# Sheet1.net
KiCad netlist of a schematic drawn in Altium Designer
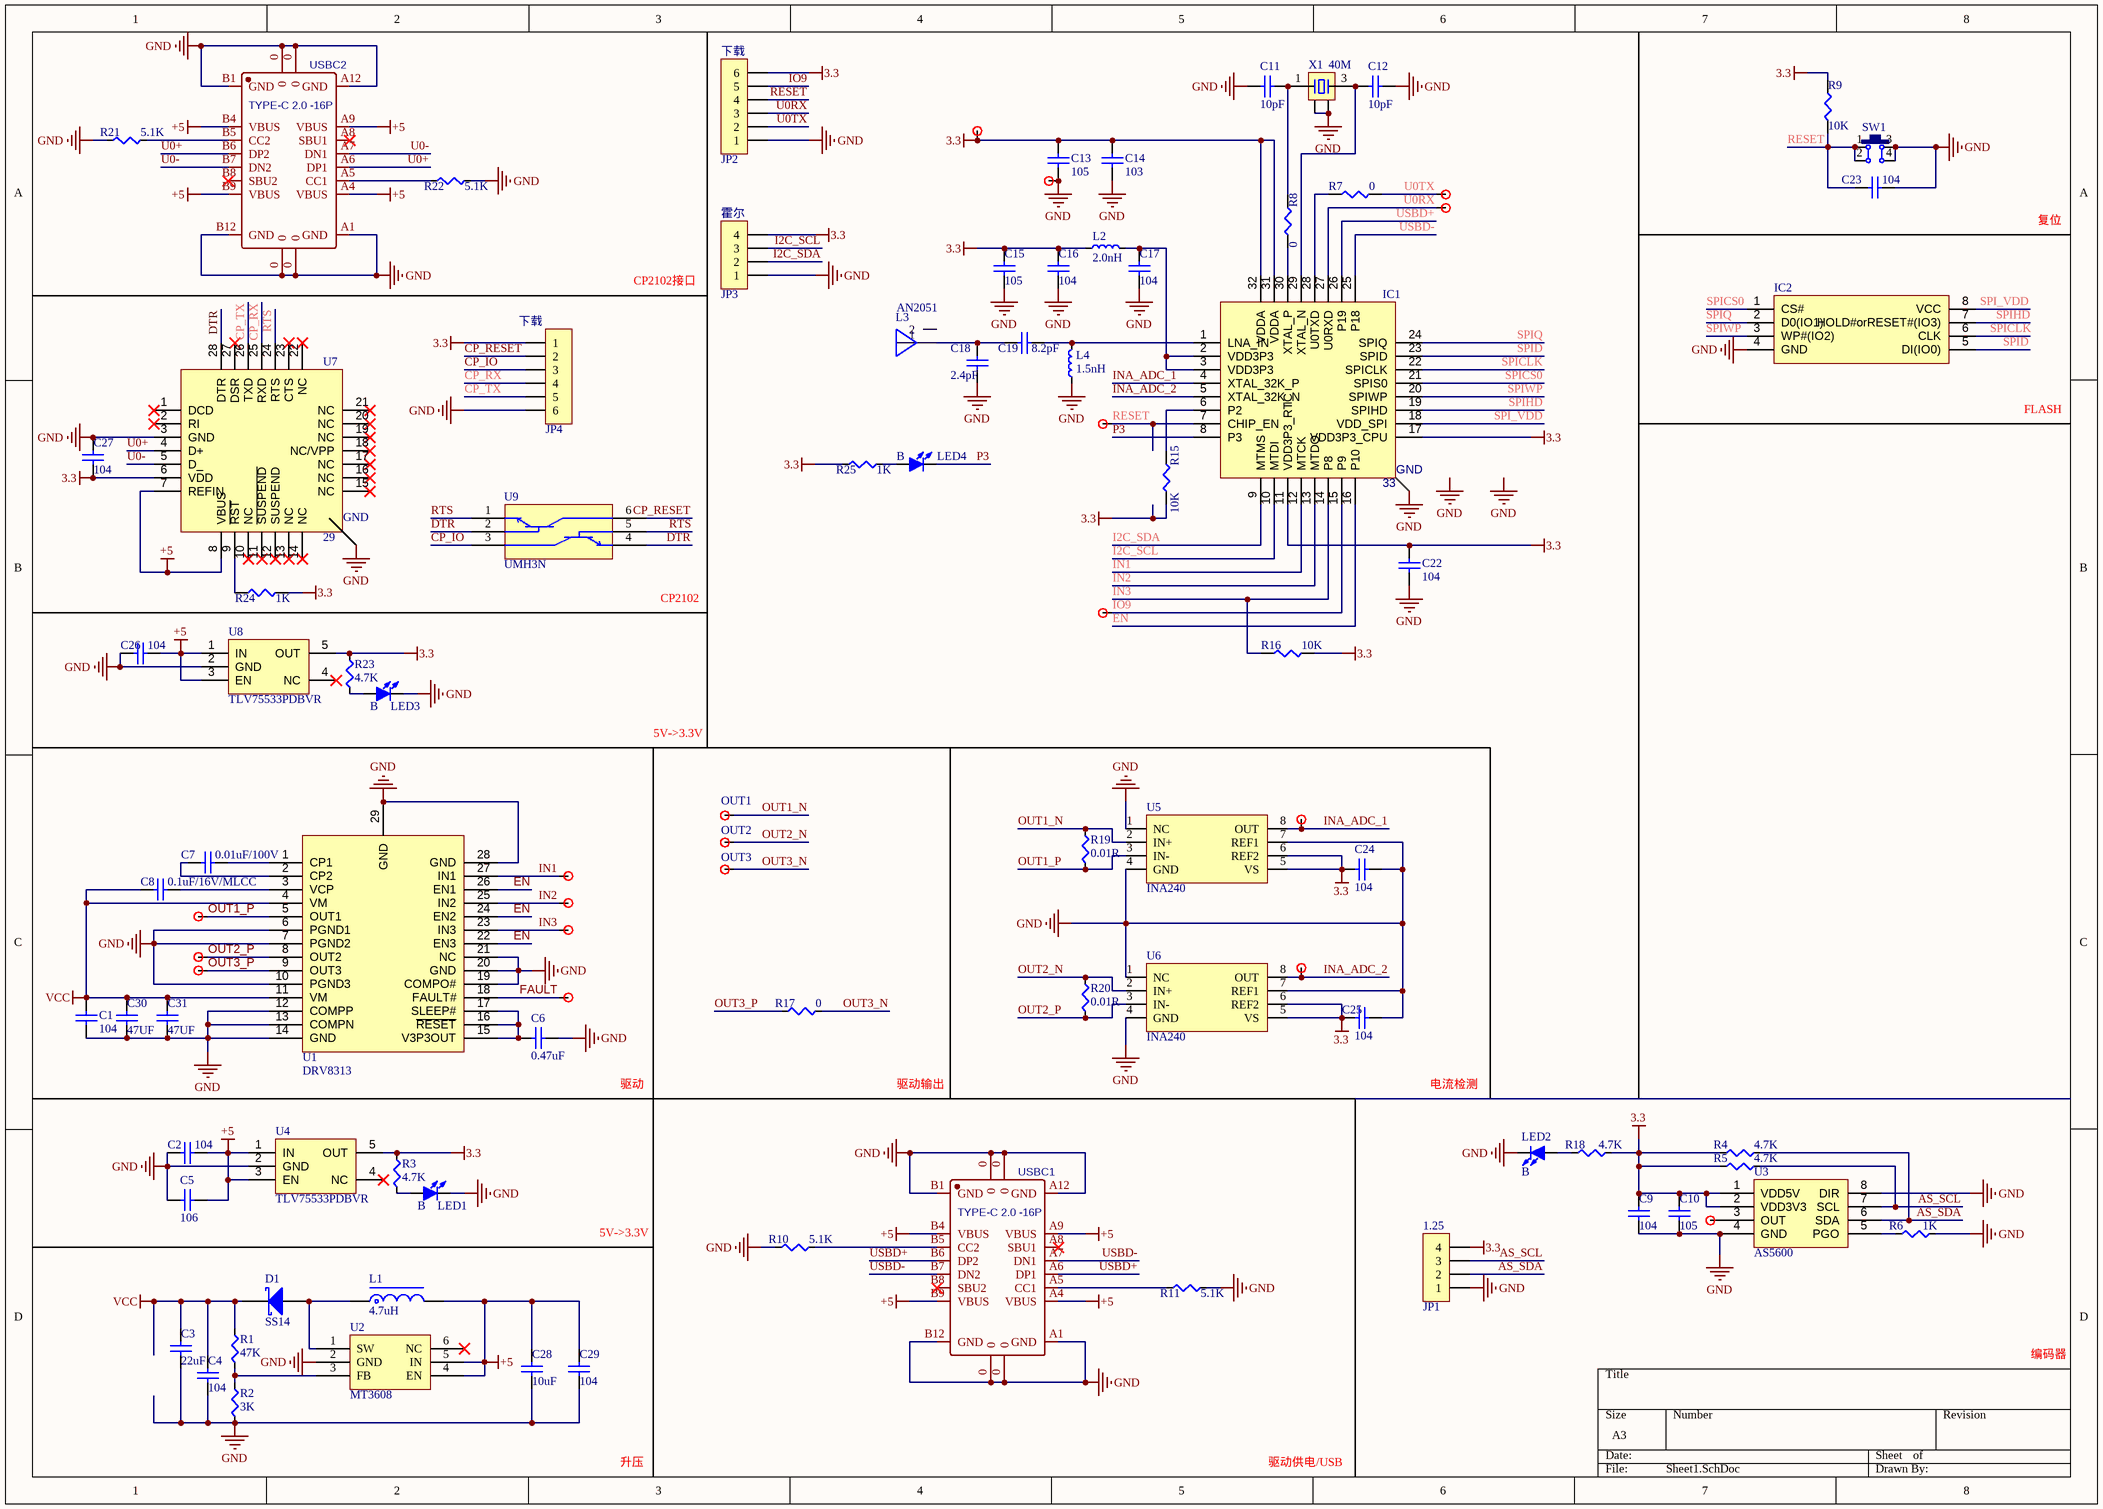
[diagram p0: Sheet1.SchDoc]

(export (version "E")
  (design (tool "Eeschema 10.0.6"))
  (components
    (comp (ref "C1")
      (value "104")
      (footprint "C 0603_L")
      (description "贴片电容")
      (libsource (lib "0.1 - 电阻-电容-电感") (part "C"))
    )
    (comp (ref "C2")
      (value "104")
      (footprint "C 0603_L")
      (description "贴片电容")
      (libsource (lib "0.1 - 电阻-电容-电感") (part "C"))
    )
    (comp (ref "C3")
      (value "22uF")
      (footprint "C 1206_L")
      (description "贴片电容")
      (libsource (lib "0.1 - 电阻-电容-电感") (part "C"))
    )
    (comp (ref "C4")
      (value "104")
      (footprint "C 0603_L")
      (description "贴片电容")
      (libsource (lib "0.1 - 电阻-电容-电感") (part "C"))
    )
    (comp (ref "C5")
      (value "106")
      (footprint "C 1206_L")
      (description "贴片电容")
      (libsource (lib "0.1 - 电阻-电容-电感") (part "C"))
    )
    (comp (ref "C6")
      (value "0.47uF")
      (footprint "C 0603_L")
      (description "贴片电容")
      (libsource (lib "0.1 - 电阻-电容-电感") (part "C"))
    )
    (comp (ref "C7")
      (value "0.01uF/100V")
      (footprint "C 0603_L")
      (description "贴片电容")
      (libsource (lib "0.1 - 电阻-电容-电感") (part "C"))
    )
    (comp (ref "C8")
      (value "0.1uF/16V/MLCC")
      (footprint "C 0603_L")
      (description "贴片电容")
      (libsource (lib "0.1 - 电阻-电容-电感") (part "C"))
    )
    (comp (ref "C9")
      (value "104")
      (footprint "C 0603_L")
      (description "贴片电容")
      (libsource (lib "0.1 - 电阻-电容-电感") (part "C"))
    )
    (comp (ref "C10")
      (value "105")
      (footprint "C 0603_L")
      (description "贴片电容")
      (libsource (lib "0.1 - 电阻-电容-电感") (part "C"))
    )
    (comp (ref "C11")
      (value "10pF")
      (footprint "C 0603_L")
      (description "贴片电容")
      (libsource (lib "0.1 - 电阻-电容-电感") (part "C"))
    )
    (comp (ref "C12")
      (value "10pF")
      (footprint "C 0603_L")
      (description "贴片电容")
      (libsource (lib "0.1 - 电阻-电容-电感") (part "C"))
    )
    (comp (ref "C13")
      (value "105")
      (footprint "C 0603_L")
      (description "贴片电容")
      (libsource (lib "0.1 - 电阻-电容-电感") (part "C"))
    )
    (comp (ref "C14")
      (value "103")
      (footprint "C 0603_L")
      (description "贴片电容")
      (libsource (lib "0.1 - 电阻-电容-电感") (part "C"))
    )
    (comp (ref "C15")
      (value "105")
      (footprint "C 0603_L")
      (description "贴片电容")
      (libsource (lib "0.1 - 电阻-电容-电感") (part "C"))
    )
    (comp (ref "C16")
      (value "104")
      (footprint "C 0603_L")
      (description "贴片电容")
      (libsource (lib "0.1 - 电阻-电容-电感") (part "C"))
    )
    (comp (ref "C17")
      (value "104")
      (footprint "C 0603_L")
      (description "贴片电容")
      (libsource (lib "0.1 - 电阻-电容-电感") (part "C"))
    )
    (comp (ref "C18")
      (value "2.4pF")
      (footprint "C 0603_L")
      (description "贴片电容")
      (libsource (lib "0.1 - 电阻-电容-电感") (part "C"))
    )
    (comp (ref "C19")
      (value "8.2pF")
      (footprint "C 0603_L")
      (description "贴片电容")
      (libsource (lib "0.1 - 电阻-电容-电感") (part "C"))
    )
    (comp (ref "C22")
      (value "104")
      (footprint "C 0603_L")
      (description "贴片电容")
      (libsource (lib "0.1 - 电阻-电容-电感") (part "C"))
    )
    (comp (ref "C23")
      (value "104")
      (footprint "C 0603_L")
      (description "贴片电容")
      (libsource (lib "0.1 - 电阻-电容-电感") (part "C"))
    )
    (comp (ref "C24")
      (value "104")
      (footprint "C 0603_L")
      (description "贴片电容")
      (libsource (lib "0.1 - 电阻-电容-电感") (part "C"))
    )
    (comp (ref "C25")
      (value "104")
      (footprint "C 0603_L")
      (description "贴片电容")
      (libsource (lib "0.1 - 电阻-电容-电感") (part "C"))
    )
    (comp (ref "C26")
      (value "104")
      (footprint "C 0603_L")
      (description "贴片电容")
      (libsource (lib "0.1 - 电阻-电容-电感") (part "C"))
    )
    (comp (ref "C27")
      (value "104")
      (footprint "C 0603_L")
      (description "贴片电容")
      (libsource (lib "0.1 - 电阻-电容-电感") (part "C"))
    )
    (comp (ref "C28")
      (value "10uF")
      (footprint "C 1206_L")
      (description "贴片电容")
      (libsource (lib "0.1 - 电阻-电容-电感") (part "C"))
    )
    (comp (ref "C29")
      (value "104")
      (footprint "C 0603_L")
      (description "贴片电容")
      (libsource (lib "0.1 - 电阻-电容-电感") (part "C"))
    )
    (comp (ref "C30")
      (value "47UF")
      (footprint "C 1206_L")
      (description "贴片电容")
      (libsource (lib "0.1 - 电阻-电容-电感") (part "C"))
    )
    (comp (ref "C31")
      (value "47UF")
      (footprint "C 1206_L")
      (description "贴片电容")
      (libsource (lib "0.1 - 电阻-电容-电感") (part "C"))
    )
    (comp (ref "D1")
      (value "SS14")
      (footprint "SMA")
      (description "肖特基二极管")
      (libsource (lib "0.2 - 二极管-整流桥") (part "SS14"))
    )
    (comp (ref "HP1")
      (value "HP")
      (footprint "HP1x0.5")
      (description "引脚测试点")
      (libsource (lib "6.6 - 焊盘") (part "HP"))
    )
    (comp (ref "HP2")
      (value "HP")
      (footprint "HP1x0.5")
      (description "引脚测试点")
      (libsource (lib "6.6 - 焊盘") (part "HP"))
    )
    (comp (ref "HP3")
      (value "HP")
      (footprint "HP1x0.5")
      (description "引脚测试点")
      (libsource (lib "6.6 - 焊盘") (part "HP"))
    )
    (comp (ref "HP4")
      (value "HP")
      (footprint "HP1x0.5")
      (description "引脚测试点")
      (libsource (lib "6.6 - 焊盘") (part "HP"))
    )
    (comp (ref "HP5")
      (value "HP")
      (footprint "HP1x0.5")
      (description "引脚测试点")
      (libsource (lib "6.6 - 焊盘") (part "HP"))
    )
    (comp (ref "HP6")
      (value "HP")
      (footprint "HP1x0.5")
      (description "引脚测试点")
      (libsource (lib "6.6 - 焊盘") (part "HP"))
    )
    (comp (ref "HP7")
      (value "HP")
      (footprint "HP1x0.5")
      (description "引脚测试点")
      (libsource (lib "6.6 - 焊盘") (part "HP"))
    )
    (comp (ref "HP8")
      (value "HP")
      (footprint "HP1x0.5")
      (description "引脚测试点")
      (libsource (lib "6.6 - 焊盘") (part "HP"))
    )
    (comp (ref "HP9")
      (value "OUT1")
      (footprint "HP1x0.5")
      (description "引脚测试点")
      (libsource (lib "6.6 - 焊盘") (part "HP"))
    )
    (comp (ref "HP10")
      (value "OUT2")
      (footprint "HP1x0.5")
      (description "引脚测试点")
      (libsource (lib "6.6 - 焊盘") (part "HP"))
    )
    (comp (ref "HP11")
      (value "OUT3")
      (footprint "HP1x0.5")
      (description "引脚测试点")
      (libsource (lib "6.6 - 焊盘") (part "HP"))
    )
    (comp (ref "HP12")
      (value "HP")
      (footprint "HP1x0.5")
      (description "引脚测试点")
      (libsource (lib "6.6 - 焊盘") (part "HP"))
    )
    (comp (ref "HP13")
      (value "HP")
      (footprint "HP1x0.5")
      (description "引脚测试点")
      (libsource (lib "6.6 - 焊盘") (part "HP"))
    )
    (comp (ref "HP14")
      (value "HP")
      (footprint "HP1x0.5")
      (description "引脚测试点")
      (libsource (lib "6.6 - 焊盘") (part "HP"))
    )
    (comp (ref "HP15")
      (value "HP")
      (footprint "HP1x0.5")
      (description "引脚测试点")
      (libsource (lib "6.6 - 焊盘") (part "HP"))
    )
    (comp (ref "HP16")
      (value "HP")
      (footprint "HP1x0.5")
      (description "引脚测试点")
      (libsource (lib "6.6 - 焊盘") (part "HP"))
    )
    (comp (ref "HP17")
      (value "HP")
      (footprint "HP1x0.5")
      (description "引脚测试点")
      (libsource (lib "6.6 - 焊盘") (part "HP"))
    )
    (comp (ref "HP18")
      (value "HP")
      (footprint "HP1x0.5")
      (description "引脚测试点")
      (libsource (lib "6.6 - 焊盘") (part "HP"))
    )
    (comp (ref "HP19")
      (value "HP")
      (footprint "HP1x0.5")
      (description "引脚测试点")
      (libsource (lib "6.6 - 焊盘") (part "HP"))
    )
    (comp (ref "IC1")
      (value "ESP32-C3")
      (footprint "ESP32-C3")
      (description "ESP32-C3 QFN-32(5x5)")
      (libsource (lib "ESP32") (part "ESP32-C3"))
    )
    (comp (ref "IC2")
      (value "W25Q64")
      (footprint "SOIC-8W")
      (libsource (lib "1.2 - 存储器-传感元件") (part "W25Q64"))
    )
    (comp (ref "JP1")
      (value "HDR-1X4")
      (footprint "MX 1.25-WI-4P")
      (description "4P接插件")
      (libsource (lib "5.0 - 接插件-脚距1.25") (part "Header 4"))
    )
    (comp (ref "JP2")
      (value "HDR-1X6")
      (footprint "MX 1.25-WI-6P")
      (description "6P接插件")
      (libsource (lib "5.0 - 接插件-脚距1.25") (part "Header 6"))
    )
    (comp (ref "JP3")
      (value "HDR-1X4")
      (footprint "MX 1.25-WI-4P")
      (description "4P接插件")
      (libsource (lib "5.0 - 接插件-脚距1.25") (part "Header 4"))
    )
    (comp (ref "JP4")
      (value "HDR-1X6")
      (footprint "MX 1.25-WI-6P")
      (description "6P接插件")
      (libsource (lib "") (part "Header 6_1"))
    )
    (comp (ref "L1")
      (value "4.7uH")
      (footprint "NR4020")
      (description "NR磁胶电感")
      (libsource (lib "0.1 - 电阻-电容-电感") (part "L-NR"))
    )
    (comp (ref "L2")
      (value "2.0nH")
      (footprint "L 0603")
      (description "小功率贴片电感")
      (libsource (lib "0.1 - 电阻-电容-电感") (part "L"))
    )
    (comp (ref "L3")
      (value "AN2051")
      (footprint "AN2051-245 2.4G")
      (description "AN2051-245 2.4G蓝牙wifi 贴片 2051")
      (libsource (lib "1.8 - WiFi天线-SMA射频座") (part "AN2051"))
    )
    (comp (ref "L4")
      (value "1.5nH")
      (footprint "L 0603")
      (description "小功率贴片电感")
      (libsource (lib "0.1 - 电阻-电容-电感") (part "L"))
    )
    (comp (ref "LED1")
      (value "B")
      (footprint "LED 0603B")
      (description "贴片LED")
      (libsource (lib "0.3 - LED发光二极管") (part "B"))
    )
    (comp (ref "LED2")
      (value "B")
      (footprint "LED 0603B")
      (description "贴片LED")
      (libsource (lib "0.3 - LED发光二极管") (part "B"))
    )
    (comp (ref "LED3")
      (value "B")
      (footprint "LED 0603B")
      (description "贴片LED")
      (libsource (lib "0.3 - LED发光二极管") (part "B"))
    )
    (comp (ref "LED4")
      (value "B")
      (footprint "LED 0603B")
      (description "贴片LED")
      (libsource (lib "0.3 - LED发光二极管") (part "B"))
    )
    (comp (ref "R1")
      (value "47K")
      (footprint "R 0603_L")
      (description "贴片电阻")
      (libsource (lib "") (part "R_1"))
    )
    (comp (ref "R2")
      (value "3K")
      (footprint "R 0603_L")
      (description "贴片电阻")
      (libsource (lib "") (part "R_1"))
    )
    (comp (ref "R3")
      (value "4.7K")
      (footprint "R 0603_L")
      (description "贴片电阻")
      (libsource (lib "") (part "R_1"))
    )
    (comp (ref "R4")
      (value "4.7K")
      (footprint "R 0603_L")
      (description "贴片电阻")
      (libsource (lib "") (part "R_1"))
    )
    (comp (ref "R5")
      (value "4.7K")
      (footprint "R 0603_L")
      (description "贴片电阻")
      (libsource (lib "") (part "R_1"))
    )
    (comp (ref "R6")
      (value "1K")
      (footprint "R 0603_L")
      (description "贴片电阻")
      (libsource (lib "") (part "R_1"))
    )
    (comp (ref "R7")
      (value "0")
      (footprint "R 0603_L")
      (description "贴片电阻")
      (libsource (lib "0.1 - 电阻-电容-电感") (part "R"))
    )
    (comp (ref "R8")
      (value "0")
      (footprint "R 0603_L")
      (description "贴片电阻")
      (libsource (lib "0.1 - 电阻-电容-电感") (part "R"))
    )
    (comp (ref "R9")
      (value "10K")
      (footprint "R 0603_L")
      (description "贴片电阻")
      (libsource (lib "0.1 - 电阻-电容-电感") (part "R"))
    )
    (comp (ref "R10")
      (value "5.1K")
      (footprint "R 0603_L")
      (description "贴片电阻")
      (libsource (lib "") (part "R_1"))
    )
    (comp (ref "R11")
      (value "5.1K")
      (footprint "R 0603_L")
      (description "贴片电阻")
      (libsource (lib "") (part "R_1"))
    )
    (comp (ref "R15")
      (value "10K")
      (footprint "R 0603_L")
      (description "贴片电阻")
      (libsource (lib "0.1 - 电阻-电容-电感") (part "R"))
    )
    (comp (ref "R16")
      (value "10K")
      (footprint "R 0603_L")
      (description "贴片电阻")
      (libsource (lib "0.1 - 电阻-电容-电感") (part "R"))
    )
    (comp (ref "R17")
      (value "0")
      (footprint "R 0603_L")
      (description "贴片电阻")
      (libsource (lib "") (part "R_1"))
    )
    (comp (ref "R18")
      (value "4.7K")
      (footprint "R 0603_L")
      (description "贴片电阻")
      (libsource (lib "") (part "R_1"))
    )
    (comp (ref "R19")
      (value "0.01R")
      (footprint "R 1206_L")
      (description "贴片电阻")
      (libsource (lib "") (part "R_1"))
    )
    (comp (ref "R20")
      (value "0.01R")
      (footprint "R 1206_L")
      (description "贴片电阻")
      (libsource (lib "") (part "R_1"))
    )
    (comp (ref "R21")
      (value "5.1K")
      (footprint "R 0603_L")
      (description "贴片电阻")
      (libsource (lib "") (part "R_1"))
    )
    (comp (ref "R22")
      (value "5.1K")
      (footprint "R 0603_L")
      (description "贴片电阻")
      (libsource (lib "") (part "R_1"))
    )
    (comp (ref "R23")
      (value "4.7K")
      (footprint "R 0603_L")
      (description "贴片电阻")
      (libsource (lib "") (part "R_1"))
    )
    (comp (ref "R24")
      (value "1K")
      (footprint "R 0603_L")
      (description "贴片电阻")
      (libsource (lib "0.1 - 电阻-电容-电感") (part "R"))
    )
    (comp (ref "R25")
      (value "1K")
      (footprint "R 0603_L")
      (description "贴片电阻")
      (libsource (lib "") (part "R_1"))
    )
    (comp (ref "SW1")
      (value "3.2x4.2x5")
      (footprint "TSW SMD 3.2*4.2*2.5")
      (description "贴片4.2*3.2轻触开关")
      (libsource (lib "0.7 - 常用按键-开关-蜂鸣器-电池") (part "TSW SMD-3.2x4.2"))
    )
    (comp (ref "U1")
      (value "DRV8313")
      (footprint "HTSSOP-28-EP-4.5mm")
      (description "DRV8313 无刷直流BLDC 8V~60V三路半H桥驱动器IC")
      (libsource (lib "1.0 - 常见芯片") (part "DRV8313"))
    )
    (comp (ref "U2")
      (value "MT3608")
      (footprint "SOT23-6L")
      (description "DCDC 升压1.2MHZ 2A\r\n97%")
      (libsource (lib "1.1 - 电源类芯片") (part "MT3608"))
    )
    (comp (ref "U3")
      (value "AS5600")
      (footprint "SOIC-8")
      (description "AS5600 12bit磁角度位置传感器")
      (libsource (lib "1.0 - 常见芯片") (part "AS5600"))
    )
    (comp (ref "U4")
      (value "TLV75533PDBVR")
      (footprint "SOT23-5L")
      (description "Vout:3.3V;Vin:1.45~5.5V,500ma;低压降")
      (libsource (lib "1.1 - 电源类芯片") (part "TLV75533PDBVR"))
    )
    (comp (ref "U5")
      (value "INA240")
      (footprint "TSSOP8_N")
      (description "具有增强的 PWM 抑制能力的 -4V 至 80V、双向、超精密电流感应放大器")
      (libsource (lib "1.1 - 电源类芯片") (part "INA240"))
    )
    (comp (ref "U6")
      (value "INA240")
      (footprint "TSSOP8_N")
      (description "具有增强的 PWM 抑制能力的 -4V 至 80V、双向、超精密电流感应放大器")
      (libsource (lib "1.1 - 电源类芯片") (part "INA240"))
    )
    (comp (ref "U7")
      (value "CP2102")
      (footprint "QFN28 5x5_M")
      (description "USB转TTL")
      (libsource (lib "1.0 - 常见芯片") (part "CP2102"))
    )
    (comp (ref "U8")
      (value "TLV75533PDBVR")
      (footprint "SOT23-5L")
      (description "Vout:3.3V;Vin:1.45~5.5V,500ma;低压降")
      (libsource (lib "1.1 - 电源类芯片") (part "TLV75533PDBVR"))
    )
    (comp (ref "U9")
      (value "UMH3N")
      (footprint "SOT-363")
      (description "2NPN预偏式(双)")
      (libsource (lib "0.4 - 三极管-场效应管-可控硅") (part "UMH3N"))
    )
    (comp (ref "USBC1")
      (value "TYPE-C 2.0 -16P")
      (footprint "USB-C-SMD_TYPE-C-USB-5")
      (description "USB2.0 Type-C 母座 16Pin")
      (libsource (lib "0.8 - 以太网-音频-USB插座") (part "USB2.0 Type-C 16Pin母座"))
    )
    (comp (ref "USBC2")
      (value "TYPE-C 2.0 -16P")
      (footprint "USB-C-SMD_TYPE-C-USB-5")
      (description "USB2.0 Type-C 母座 16Pin")
      (libsource (lib "0.8 - 以太网-音频-USB插座") (part "USB2.0 Type-C 16Pin母座"))
    )
    (comp (ref "X1")
      (value "40M")
      (footprint "OSC 3225-4P")
      (description "4脚无源晶振")
      (libsource (lib "0.5 - 保险丝-晶振-光耦") (part "XTAL-4P"))
    )
  )
  (nets
    (net (code "1") (name "+5") (class "Default")
      (node (ref "C2") (pin "2") (pinfunction "2_2") (pintype "passive"))
      (node (ref "C26") (pin "2") (pinfunction "2_2") (pintype "passive"))
      (node (ref "C28") (pin "2") (pinfunction "2_2") (pintype "passive"))
      (node (ref "C29") (pin "2") (pinfunction "2_2") (pintype "passive"))
      (node (ref "C5") (pin "1") (pinfunction "1_1") (pintype "passive"))
      (node (ref "L1") (pin "2") (pinfunction "2_2") (pintype "passive"))
      (node (ref "U2") (pin "4") (pinfunction "EN_4") (pintype "passive"))
      (node (ref "U2") (pin "5") (pinfunction "IN_5") (pintype "passive"))
      (node (ref "U4") (pin "1") (pinfunction "IN_1") (pintype "passive"))
      (node (ref "U4") (pin "3") (pinfunction "EN_3") (pintype "passive"))
      (node (ref "U7") (pin "7") (pinfunction "REFIN_7") (pintype "passive"))
      (node (ref "U7") (pin "8") (pinfunction "VBUS_8") (pintype "passive"))
      (node (ref "U8") (pin "1") (pinfunction "IN_1") (pintype "passive"))
      (node (ref "U8") (pin "3") (pinfunction "EN_3") (pintype "passive"))
      (node (ref "USBC1") (pin "A4") (pinfunction "VBUS_A4") (pintype "passive"))
      (node (ref "USBC1") (pin "A9") (pinfunction "VBUS_A9") (pintype "passive"))
      (node (ref "USBC1") (pin "B4") (pinfunction "VBUS_B4") (pintype "passive"))
      (node (ref "USBC1") (pin "B9") (pinfunction "VBUS_B9") (pintype "passive"))
      (node (ref "USBC2") (pin "A4") (pinfunction "VBUS_A4") (pintype "passive"))
      (node (ref "USBC2") (pin "A9") (pinfunction "VBUS_A9") (pintype "passive"))
      (node (ref "USBC2") (pin "B4") (pinfunction "VBUS_B4") (pintype "passive"))
      (node (ref "USBC2") (pin "B9") (pinfunction "VBUS_B9") (pintype "passive"))
    )
    (net (code "2") (name "/AS_SCL") (class "Default")
      (node (ref "JP1") (pin "3") (pinfunction "3_3") (pintype "passive"))
      (node (ref "R5") (pin "2") (pinfunction "2_2") (pintype "passive"))
      (node (ref "U3") (pin "7") (pinfunction "SCL_7") (pintype "passive"))
    )
    (net (code "3") (name "/AS_SDA") (class "Default")
      (node (ref "JP1") (pin "2") (pinfunction "2_2") (pintype "passive"))
      (node (ref "R4") (pin "2") (pinfunction "2_2") (pintype "passive"))
      (node (ref "U3") (pin "6") (pinfunction "SDA_6") (pintype "passive"))
    )
    (net (code "4") (name "/CP_IO") (class "Default")
      (node (ref "JP4") (pin "3") (pinfunction "3_3") (pintype "passive"))
      (node (ref "U9") (pin "3") (pinfunction "C2_3") (pintype "passive"))
    )
    (net (code "5") (name "/CP_RESET") (class "Default")
      (node (ref "JP4") (pin "2") (pinfunction "2_2") (pintype "passive"))
      (node (ref "U9") (pin "6") (pinfunction "C1_6") (pintype "passive"))
    )
    (net (code "6") (name "/CP_RX") (class "Default")
      (node (ref "JP4") (pin "4") (pinfunction "4_4") (pintype "passive"))
      (node (ref "U7") (pin "25") (pinfunction "RXD_25") (pintype "passive"))
    )
    (net (code "7") (name "/CP_TX") (class "Default")
      (node (ref "JP4") (pin "5") (pinfunction "5_5") (pintype "passive"))
      (node (ref "U7") (pin "26") (pinfunction "TXD_26") (pintype "passive"))
    )
    (net (code "8") (name "/DTR") (class "Default")
      (node (ref "U7") (pin "28") (pinfunction "DTR_28") (pintype "passive"))
      (node (ref "U9") (pin "2") (pinfunction "B2_2") (pintype "passive"))
      (node (ref "U9") (pin "4") (pinfunction "E2_4") (pintype "passive"))
    )
    (net (code "9") (name "/EN") (class "Default")
      (node (ref "IC1") (pin "16") (pinfunction "P10_16") (pintype "power_in"))
      (node (ref "U1") (pin "22") (pinfunction "EN3_22") (pintype "passive"))
      (node (ref "U1") (pin "24") (pinfunction "EN2_24") (pintype "passive"))
      (node (ref "U1") (pin "26") (pinfunction "EN1_26") (pintype "passive"))
    )
    (net (code "10") (name "/FAULT") (class "Default")
      (node (ref "HP7") (pin "1") (pinfunction "1_1") (pintype "passive"))
      (node (ref "U1") (pin "18") (pinfunction "FAULT#_18") (pintype "passive"))
    )
    (net (code "11") (name "/I2C_SCL") (class "Default")
      (node (ref "IC1") (pin "10") (pinfunction "MTDI_10") (pintype "power_in"))
      (node (ref "JP3") (pin "3") (pinfunction "3_3") (pintype "passive"))
    )
    (net (code "12") (name "/I2C_SDA") (class "Default")
      (node (ref "IC1") (pin "9") (pinfunction "MTMS_9") (pintype "power_in"))
      (node (ref "JP3") (pin "2") (pinfunction "2_2") (pintype "passive"))
    )
    (net (code "13") (name "/IN1") (class "Default")
      (node (ref "HP1") (pin "1") (pinfunction "1_1") (pintype "passive"))
      (node (ref "IC1") (pin "12") (pinfunction "MTCK_12") (pintype "power_in"))
      (node (ref "U1") (pin "27") (pinfunction "IN1_27") (pintype "passive"))
    )
    (net (code "14") (name "/IN2") (class "Default")
      (node (ref "HP2") (pin "1") (pinfunction "1_1") (pintype "passive"))
      (node (ref "IC1") (pin "13") (pinfunction "MTDO_13") (pintype "power_in"))
      (node (ref "U1") (pin "25") (pinfunction "IN2_25") (pintype "passive"))
    )
    (net (code "15") (name "/IN3") (class "Default")
      (node (ref "HP4") (pin "1") (pinfunction "1_1") (pintype "passive"))
      (node (ref "IC1") (pin "14") (pinfunction "P8_14") (pintype "power_in"))
      (node (ref "R16") (pin "1") (pinfunction "1_1") (pintype "passive"))
      (node (ref "U1") (pin "23") (pinfunction "IN3_23") (pintype "passive"))
    )
    (net (code "16") (name "/INA_ADC_1") (class "Default")
      (node (ref "HP12") (pin "1") (pinfunction "1_1") (pintype "passive"))
      (node (ref "IC1") (pin "4") (pinfunction "XTAL_32K_P_4") (pintype "power_in"))
      (node (ref "U5") (pin "8") (pinfunction "OUT_8") (pintype "passive"))
    )
    (net (code "17") (name "/INA_ADC_2") (class "Default")
      (node (ref "HP14") (pin "1") (pinfunction "1_1") (pintype "passive"))
      (node (ref "IC1") (pin "5") (pinfunction "XTAL_32K_N_5") (pintype "power_in"))
      (node (ref "U6") (pin "8") (pinfunction "OUT_8") (pintype "passive"))
    )
    (net (code "18") (name "/IO9") (class "Default")
      (node (ref "HP17") (pin "1") (pinfunction "1_1") (pintype "passive"))
      (node (ref "IC1") (pin "15") (pinfunction "P9_15") (pintype "power_in"))
      (node (ref "JP2") (pin "5") (pinfunction "5_5") (pintype "passive"))
    )
    (net (code "19") (name "/OUT1_N") (class "Default")
      (node (ref "HP9") (pin "1") (pinfunction "1_1") (pintype "passive"))
      (node (ref "R19") (pin "2") (pinfunction "2_2") (pintype "passive"))
      (node (ref "U5") (pin "2") (pinfunction "IN+_2") (pintype "passive"))
    )
    (net (code "20") (name "/OUT1_P") (class "Default")
      (node (ref "HP3") (pin "1") (pinfunction "1_1") (pintype "passive"))
      (node (ref "R19") (pin "1") (pinfunction "1_1") (pintype "passive"))
      (node (ref "U1") (pin "5") (pinfunction "OUT1_5") (pintype "passive"))
      (node (ref "U5") (pin "3") (pinfunction "IN-_3") (pintype "passive"))
    )
    (net (code "21") (name "/OUT2_N") (class "Default")
      (node (ref "HP10") (pin "1") (pinfunction "1_1") (pintype "passive"))
      (node (ref "R20") (pin "2") (pinfunction "2_2") (pintype "passive"))
      (node (ref "U6") (pin "2") (pinfunction "IN+_2") (pintype "passive"))
    )
    (net (code "22") (name "/OUT2_P") (class "Default")
      (node (ref "HP5") (pin "1") (pinfunction "1_1") (pintype "passive"))
      (node (ref "R20") (pin "1") (pinfunction "1_1") (pintype "passive"))
      (node (ref "U1") (pin "8") (pinfunction "OUT2_8") (pintype "passive"))
      (node (ref "U6") (pin "3") (pinfunction "IN-_3") (pintype "passive"))
    )
    (net (code "23") (name "/OUT3_N") (class "Default")
      (node (ref "HP11") (pin "1") (pinfunction "1_1") (pintype "passive"))
      (node (ref "R17") (pin "2") (pinfunction "2_2") (pintype "passive"))
    )
    (net (code "24") (name "/OUT3_P") (class "Default")
      (node (ref "HP6") (pin "1") (pinfunction "1_1") (pintype "passive"))
      (node (ref "R17") (pin "1") (pinfunction "1_1") (pintype "passive"))
      (node (ref "U1") (pin "9") (pinfunction "OUT3_9") (pintype "passive"))
    )
    (net (code "25") (name "/P3") (class "Default")
      (node (ref "IC1") (pin "8") (pinfunction "P3_8") (pintype "power_in"))
      (node (ref "LED4") (pin "2") (pinfunction "K_2") (pintype "passive"))
    )
    (net (code "26") (name "/RESET") (class "Default")
      (node (ref "C23") (pin "1") (pinfunction "1_1") (pintype "passive"))
      (node (ref "HP16") (pin "1") (pinfunction "1_1") (pintype "passive"))
      (node (ref "IC1") (pin "7") (pinfunction "CHIP_EN_7") (pintype "power_in"))
      (node (ref "JP2") (pin "4") (pinfunction "4_4") (pintype "passive"))
      (node (ref "R9") (pin "1") (pinfunction "1_1") (pintype "passive"))
      (node (ref "SW1") (pin "1") (pinfunction "1_1") (pintype "passive"))
      (node (ref "SW1") (pin "2") (pinfunction "2_2") (pintype "passive"))
    )
    (net (code "27") (name "/RTS") (class "Default")
      (node (ref "U7") (pin "24") (pinfunction "RTS_24") (pintype "passive"))
      (node (ref "U9") (pin "1") (pinfunction "E1_1") (pintype "passive"))
      (node (ref "U9") (pin "5") (pinfunction "B2_5") (pintype "passive"))
    )
    (net (code "28") (name "/SPICLK") (class "Default")
      (node (ref "IC1") (pin "22") (pinfunction "SPICLK_22") (pintype "power_in"))
      (node (ref "IC2") (pin "6") (pinfunction "CLK_6") (pintype "power_in"))
    )
    (net (code "29") (name "/SPICS0") (class "Default")
      (node (ref "IC1") (pin "21") (pinfunction "SPIS0_21") (pintype "power_in"))
      (node (ref "IC2") (pin "1") (pinfunction "CS#_1") (pintype "power_in"))
    )
    (net (code "30") (name "/SPID") (class "Default")
      (node (ref "IC1") (pin "23") (pinfunction "SPID_23") (pintype "power_in"))
      (node (ref "IC2") (pin "5") (pinfunction "DI(IO0)_5") (pintype "power_in"))
    )
    (net (code "31") (name "/SPIHD") (class "Default")
      (node (ref "IC1") (pin "19") (pinfunction "SPIHD_19") (pintype "power_in"))
      (node (ref "IC2") (pin "7") (pinfunction "HOLD#orRESET#(IO3)_7") (pintype "power_in"))
    )
    (net (code "32") (name "/SPIQ") (class "Default")
      (node (ref "IC1") (pin "24") (pinfunction "SPIQ_24") (pintype "power_in"))
      (node (ref "IC2") (pin "2") (pinfunction "D0(IO1)_2") (pintype "power_in"))
    )
    (net (code "33") (name "/SPIWP") (class "Default")
      (node (ref "IC1") (pin "20") (pinfunction "SPIWP_20") (pintype "power_in"))
      (node (ref "IC2") (pin "3") (pinfunction "WP#(IO2)_3") (pintype "power_in"))
    )
    (net (code "34") (name "/SPI_VDD") (class "Default")
      (node (ref "IC1") (pin "18") (pinfunction "VDD_SPI_18") (pintype "power_in"))
      (node (ref "IC2") (pin "8") (pinfunction "VCC_8") (pintype "power_in"))
    )
    (net (code "35") (name "/U0+") (class "Default")
      (node (ref "U7") (pin "4") (pinfunction "D+_4") (pintype "passive"))
      (node (ref "USBC2") (pin "A6") (pinfunction "DP1_A6") (pintype "passive"))
      (node (ref "USBC2") (pin "B6") (pinfunction "DP2_B6") (pintype "passive"))
    )
    (net (code "36") (name "/U0-") (class "Default")
      (node (ref "U7") (pin "5") (pinfunction "D__5") (pintype "passive"))
      (node (ref "USBC2") (pin "A7") (pinfunction "DN1_A7") (pintype "passive"))
      (node (ref "USBC2") (pin "B7") (pinfunction "DN2_B7") (pintype "passive"))
    )
    (net (code "37") (name "/U0RX") (class "Default")
      (node (ref "HP15") (pin "1") (pinfunction "1_1") (pintype "passive"))
      (node (ref "IC1") (pin "27") (pinfunction "U0RXD_27") (pintype "power_in"))
      (node (ref "JP2") (pin "3") (pinfunction "3_3") (pintype "passive"))
    )
    (net (code "38") (name "/U0TX") (class "Default")
      (node (ref "HP13") (pin "1") (pinfunction "1_1") (pintype "passive"))
      (node (ref "JP2") (pin "2") (pinfunction "2_2") (pintype "passive"))
      (node (ref "R7") (pin "2") (pinfunction "2_2") (pintype "passive"))
    )
    (net (code "39") (name "/USBD+") (class "Default")
      (node (ref "IC1") (pin "26") (pinfunction "P19_26") (pintype "power_in"))
      (node (ref "USBC1") (pin "A6") (pinfunction "DP1_A6") (pintype "passive"))
      (node (ref "USBC1") (pin "B6") (pinfunction "DP2_B6") (pintype "passive"))
    )
    (net (code "40") (name "/USBD-") (class "Default")
      (node (ref "IC1") (pin "25") (pinfunction "P18_25") (pintype "power_in"))
      (node (ref "USBC1") (pin "A7") (pinfunction "DN1_A7") (pintype "passive"))
      (node (ref "USBC1") (pin "B7") (pinfunction "DN2_B7") (pintype "passive"))
    )
    (net (code "41") (name "3.3") (class "Default")
      (node (ref "C10") (pin "2") (pinfunction "2_2") (pintype "passive"))
      (node (ref "C13") (pin "2") (pinfunction "2_2") (pintype "passive"))
      (node (ref "C14") (pin "2") (pinfunction "2_2") (pintype "passive"))
      (node (ref "C15") (pin "2") (pinfunction "2_2") (pintype "passive"))
      (node (ref "C16") (pin "2") (pinfunction "2_2") (pintype "passive"))
      (node (ref "C22") (pin "2") (pinfunction "2_2") (pintype "passive"))
      (node (ref "C24") (pin "2") (pinfunction "2_2") (pintype "passive"))
      (node (ref "C25") (pin "1") (pinfunction "1_1") (pintype "passive"))
      (node (ref "C27") (pin "1") (pinfunction "1_1") (pintype "passive"))
      (node (ref "C9") (pin "2") (pinfunction "2_2") (pintype "passive"))
      (node (ref "HP18") (pin "1") (pinfunction "1_1") (pintype "passive"))
      (node (ref "IC1") (pin "11") (pinfunction "VDD3P3_RTC_11") (pintype "power_in"))
      (node (ref "IC1") (pin "17") (pinfunction "VDD3P3_CPU_17") (pintype "power_in"))
      (node (ref "IC1") (pin "31") (pinfunction "VDDA_31") (pintype "power_in"))
      (node (ref "IC1") (pin "32") (pinfunction "VDDA_32") (pintype "power_in"))
      (node (ref "JP1") (pin "4") (pinfunction "4_4") (pintype "passive"))
      (node (ref "JP2") (pin "6") (pinfunction "6_6") (pintype "passive"))
      (node (ref "JP3") (pin "4") (pinfunction "4_4") (pintype "passive"))
      (node (ref "JP4") (pin "1") (pinfunction "1_1") (pintype "passive"))
      (node (ref "L2") (pin "1") (pinfunction "1_1") (pintype "passive"))
      (node (ref "R15") (pin "1") (pinfunction "1_1") (pintype "passive"))
      (node (ref "R16") (pin "2") (pinfunction "2_2") (pintype "passive"))
      (node (ref "R18") (pin "2") (pinfunction "2_2") (pintype "passive"))
      (node (ref "R23") (pin "2") (pinfunction "2_2") (pintype "passive"))
      (node (ref "R24") (pin "1") (pinfunction "1_1") (pintype "passive"))
      (node (ref "R25") (pin "1") (pinfunction "1_1") (pintype "passive"))
      (node (ref "R3") (pin "2") (pinfunction "2_2") (pintype "passive"))
      (node (ref "R4") (pin "1") (pinfunction "1_1") (pintype "passive"))
      (node (ref "R5") (pin "1") (pinfunction "1_1") (pintype "passive"))
      (node (ref "R9") (pin "2") (pinfunction "2_2") (pintype "passive"))
      (node (ref "U3") (pin "1") (pinfunction "VDD5V_1") (pintype "passive"))
      (node (ref "U3") (pin "2") (pinfunction "VDD3V3_2") (pintype "passive"))
      (node (ref "U4") (pin "5") (pinfunction "OUT_5") (pintype "passive"))
      (node (ref "U5") (pin "5") (pinfunction "VS_5") (pintype "passive"))
      (node (ref "U5") (pin "6") (pinfunction "REF2_6") (pintype "passive"))
      (node (ref "U6") (pin "5") (pinfunction "VS_5") (pintype "passive"))
      (node (ref "U6") (pin "6") (pinfunction "REF2_6") (pintype "passive"))
      (node (ref "U7") (pin "6") (pinfunction "VDD_6") (pintype "passive"))
      (node (ref "U8") (pin "5") (pinfunction "OUT_5") (pintype "passive"))
    )
    (net (code "42") (name "GND") (class "Default")
      (node (ref "C1") (pin "1") (pinfunction "1_1") (pintype "passive"))
      (node (ref "C10") (pin "1") (pinfunction "1_1") (pintype "passive"))
      (node (ref "C11") (pin "1") (pinfunction "1_1") (pintype "passive"))
      (node (ref "C12") (pin "2") (pinfunction "2_2") (pintype "passive"))
      (node (ref "C13") (pin "1") (pinfunction "1_1") (pintype "passive"))
      (node (ref "C14") (pin "1") (pinfunction "1_1") (pintype "passive"))
      (node (ref "C15") (pin "1") (pinfunction "1_1") (pintype "passive"))
      (node (ref "C16") (pin "1") (pinfunction "1_1") (pintype "passive"))
      (node (ref "C17") (pin "1") (pinfunction "1_1") (pintype "passive"))
      (node (ref "C18") (pin "1") (pinfunction "1_1") (pintype "passive"))
      (node (ref "C2") (pin "1") (pinfunction "1_1") (pintype "passive"))
      (node (ref "C22") (pin "1") (pinfunction "1_1") (pintype "passive"))
      (node (ref "C23") (pin "2") (pinfunction "2_2") (pintype "passive"))
      (node (ref "C24") (pin "1") (pinfunction "1_1") (pintype "passive"))
      (node (ref "C25") (pin "2") (pinfunction "2_2") (pintype "passive"))
      (node (ref "C26") (pin "1") (pinfunction "1_1") (pintype "passive"))
      (node (ref "C27") (pin "2") (pinfunction "2_2") (pintype "passive"))
      (node (ref "C28") (pin "1") (pinfunction "1_1") (pintype "passive"))
      (node (ref "C29") (pin "1") (pinfunction "1_1") (pintype "passive"))
      (node (ref "C3") (pin "1") (pinfunction "1_1") (pintype "passive"))
      (node (ref "C30") (pin "1") (pinfunction "1_1") (pintype "passive"))
      (node (ref "C31") (pin "1") (pinfunction "1_1") (pintype "passive"))
      (node (ref "C4") (pin "1") (pinfunction "1_1") (pintype "passive"))
      (node (ref "C5") (pin "2") (pinfunction "2_2") (pintype "passive"))
      (node (ref "C6") (pin "1") (pinfunction "1_1") (pintype "passive"))
      (node (ref "C9") (pin "1") (pinfunction "1_1") (pintype "passive"))
      (node (ref "HP19") (pin "1") (pinfunction "1_1") (pintype "passive"))
      (node (ref "IC1") (pin "33") (pinfunction "GND_33") (pintype "power_in"))
      (node (ref "IC2") (pin "4") (pinfunction "GND_4") (pintype "power_in"))
      (node (ref "JP1") (pin "1") (pinfunction "1_1") (pintype "passive"))
      (node (ref "JP2") (pin "1") (pinfunction "1_1") (pintype "passive"))
      (node (ref "JP3") (pin "1") (pinfunction "1_1") (pintype "passive"))
      (node (ref "JP4") (pin "6") (pinfunction "6_6") (pintype "passive"))
      (node (ref "L4") (pin "1") (pinfunction "1_1") (pintype "passive"))
      (node (ref "LED1") (pin "2") (pinfunction "K_2") (pintype "passive"))
      (node (ref "LED2") (pin "2") (pinfunction "K_2") (pintype "passive"))
      (node (ref "LED3") (pin "2") (pinfunction "K_2") (pintype "passive"))
      (node (ref "R10") (pin "1") (pinfunction "1_1") (pintype "passive"))
      (node (ref "R11") (pin "2") (pinfunction "2_2") (pintype "passive"))
      (node (ref "R2") (pin "1") (pinfunction "1_1") (pintype "passive"))
      (node (ref "R21") (pin "1") (pinfunction "1_1") (pintype "passive"))
      (node (ref "R22") (pin "2") (pinfunction "2_2") (pintype "passive"))
      (node (ref "R6") (pin "2") (pinfunction "2_2") (pintype "passive"))
      (node (ref "SW1") (pin "3") (pinfunction "3_3") (pintype "passive"))
      (node (ref "SW1") (pin "4") (pinfunction "4_4") (pintype "passive"))
      (node (ref "U1") (pin "10") (pinfunction "PGND3_10") (pintype "passive"))
      (node (ref "U1") (pin "12") (pinfunction "COMPP_12") (pintype "passive"))
      (node (ref "U1") (pin "13") (pinfunction "COMPN_13") (pintype "passive"))
      (node (ref "U1") (pin "14") (pinfunction "GND_14") (pintype "passive"))
      (node (ref "U1") (pin "19") (pinfunction "COMPO#_19") (pintype "passive"))
      (node (ref "U1") (pin "20") (pinfunction "GND_20") (pintype "passive"))
      (node (ref "U1") (pin "21") (pinfunction "NC_21") (pintype "passive"))
      (node (ref "U1") (pin "28") (pinfunction "GND_28") (pintype "passive"))
      (node (ref "U1") (pin "29") (pinfunction "GND_29") (pintype "passive"))
      (node (ref "U1") (pin "6") (pinfunction "PGND1_6") (pintype "passive"))
      (node (ref "U1") (pin "7") (pinfunction "PGND2_7") (pintype "passive"))
      (node (ref "U2") (pin "2") (pinfunction "GND_2") (pintype "passive"))
      (node (ref "U3") (pin "4") (pinfunction "GND_4") (pintype "passive"))
      (node (ref "U3") (pin "8") (pinfunction "DIR_8") (pintype "passive"))
      (node (ref "U4") (pin "2") (pinfunction "GND_2") (pintype "passive"))
      (node (ref "U5") (pin "1") (pinfunction "NC_1") (pintype "passive"))
      (node (ref "U5") (pin "4") (pinfunction "GND_4") (pintype "passive"))
      (node (ref "U5") (pin "7") (pinfunction "REF1_7") (pintype "passive"))
      (node (ref "U6") (pin "1") (pinfunction "NC_1") (pintype "passive"))
      (node (ref "U6") (pin "4") (pinfunction "GND_4") (pintype "passive"))
      (node (ref "U6") (pin "7") (pinfunction "REF1_7") (pintype "passive"))
      (node (ref "U7") (pin "29") (pinfunction "GND_29") (pintype "passive"))
      (node (ref "U7") (pin "3") (pinfunction "GND_3") (pintype "passive"))
      (node (ref "U8") (pin "2") (pinfunction "GND_2") (pintype "passive"))
      (node (ref "USBC1") (pin "0") (pinfunction "0_0") (pintype "passive"))
      (node (ref "USBC1") (pin "A1") (pinfunction "GND_A1") (pintype "passive"))
      (node (ref "USBC1") (pin "A12") (pinfunction "GND_A12") (pintype "passive"))
      (node (ref "USBC1") (pin "B1") (pinfunction "GND_B1") (pintype "passive"))
      (node (ref "USBC1") (pin "B12") (pinfunction "GND_B12") (pintype "passive"))
      (node (ref "USBC2") (pin "0") (pinfunction "0_0") (pintype "passive"))
      (node (ref "USBC2") (pin "A1") (pinfunction "GND_A1") (pintype "passive"))
      (node (ref "USBC2") (pin "A12") (pinfunction "GND_A12") (pintype "passive"))
      (node (ref "USBC2") (pin "B1") (pinfunction "GND_B1") (pintype "passive"))
      (node (ref "USBC2") (pin "B12") (pinfunction "GND_B12") (pintype "passive"))
      (node (ref "X1") (pin "2") (pinfunction "2_2") (pintype "passive"))
      (node (ref "X1") (pin "4") (pinfunction "4_4") (pintype "passive"))
    )
    (net (code "43") (name "Net-(C11-Pad2)") (class "Default")
      (node (ref "C11") (pin "2") (pinfunction "2_2") (pintype "passive"))
      (node (ref "R8") (pin "2") (pinfunction "2_2") (pintype "passive"))
      (node (ref "X1") (pin "1") (pinfunction "1_1") (pintype "passive"))
    )
    (net (code "44") (name "Net-(C17-Pad2)") (class "Default")
      (node (ref "C17") (pin "2") (pinfunction "2_2") (pintype "passive"))
      (node (ref "IC1") (pin "2") (pinfunction "VDD3P3_2") (pintype "power_in"))
      (node (ref "IC1") (pin "3") (pinfunction "VDD3P3_3") (pintype "power_in"))
      (node (ref "L2") (pin "2") (pinfunction "2_2") (pintype "passive"))
    )
    (net (code "45") (name "Net-(C18-Pad2)") (class "Default")
      (node (ref "C18") (pin "2") (pinfunction "2_2") (pintype "passive"))
      (node (ref "C19") (pin "2") (pinfunction "2_2") (pintype "passive"))
      (node (ref "L3") (pin "1") (pinfunction "1_1") (pintype "passive"))
    )
    (net (code "46") (name "Net-(D1-A)") (class "Default")
      (node (ref "D1") (pin "1") (pinfunction "A_1") (pintype "passive"))
      (node (ref "L1") (pin "1") (pinfunction "1_1") (pintype "passive"))
      (node (ref "U2") (pin "1") (pinfunction "SW_1") (pintype "passive"))
    )
    (net (code "47") (name "Net-(IC1-LNA_IN)") (class "Default")
      (node (ref "C19") (pin "1") (pinfunction "1_1") (pintype "passive"))
      (node (ref "IC1") (pin "1") (pinfunction "LNA_IN_1") (pintype "power_in"))
      (node (ref "L4") (pin "2") (pinfunction "2_2") (pintype "passive"))
    )
    (net (code "48") (name "Net-(IC1-P2)") (class "Default")
      (node (ref "IC1") (pin "6") (pinfunction "P2_6") (pintype "power_in"))
      (node (ref "R15") (pin "2") (pinfunction "2_2") (pintype "passive"))
    )
    (net (code "49") (name "Net-(IC1-U0TXD)") (class "Default")
      (node (ref "IC1") (pin "28") (pinfunction "U0TXD_28") (pintype "power_in"))
      (node (ref "R7") (pin "1") (pinfunction "1_1") (pintype "passive"))
    )
    (net (code "50") (name "Net-(IC1-XTAL_N)") (class "Default")
      (node (ref "C12") (pin "1") (pinfunction "1_1") (pintype "passive"))
      (node (ref "IC1") (pin "29") (pinfunction "XTAL_N_29") (pintype "power_in"))
      (node (ref "X1") (pin "3") (pinfunction "3_3") (pintype "passive"))
    )
    (net (code "51") (name "Net-(IC1-XTAL_P)") (class "Default")
      (node (ref "IC1") (pin "30") (pinfunction "XTAL_P_30") (pintype "power_in"))
      (node (ref "R8") (pin "1") (pinfunction "1_1") (pintype "passive"))
    )
    (net (code "52") (name "Net-(LED1-A)") (class "Default")
      (node (ref "LED1") (pin "1") (pinfunction "A_1") (pintype "passive"))
      (node (ref "R3") (pin "1") (pinfunction "1_1") (pintype "passive"))
    )
    (net (code "53") (name "Net-(LED2-A)") (class "Default")
      (node (ref "LED2") (pin "1") (pinfunction "A_1") (pintype "passive"))
      (node (ref "R18") (pin "1") (pinfunction "1_1") (pintype "passive"))
    )
    (net (code "54") (name "Net-(LED3-A)") (class "Default")
      (node (ref "LED3") (pin "1") (pinfunction "A_1") (pintype "passive"))
      (node (ref "R23") (pin "1") (pinfunction "1_1") (pintype "passive"))
    )
    (net (code "55") (name "Net-(LED4-A)") (class "Default")
      (node (ref "LED4") (pin "1") (pinfunction "A_1") (pintype "passive"))
      (node (ref "R25") (pin "2") (pinfunction "2_2") (pintype "passive"))
    )
    (net (code "56") (name "Net-(U1-CP1)") (class "Default")
      (node (ref "C7") (pin "1") (pinfunction "1_1") (pintype "passive"))
      (node (ref "U1") (pin "1") (pinfunction "CP1_1") (pintype "passive"))
    )
    (net (code "57") (name "Net-(U1-CP2)") (class "Default")
      (node (ref "C7") (pin "2") (pinfunction "2_2") (pintype "passive"))
      (node (ref "U1") (pin "2") (pinfunction "CP2_2") (pintype "passive"))
    )
    (net (code "58") (name "Net-(U1-SLEEP#)") (class "Default")
      (node (ref "C6") (pin "2") (pinfunction "2_2") (pintype "passive"))
      (node (ref "U1") (pin "15") (pinfunction "V3P3OUT_15") (pintype "passive"))
      (node (ref "U1") (pin "16") (pinfunction "~{RESET}_16") (pintype "passive"))
      (node (ref "U1") (pin "17") (pinfunction "SLEEP#_17") (pintype "passive"))
    )
    (net (code "59") (name "Net-(U1-VCP)") (class "Default")
      (node (ref "C8") (pin "2") (pinfunction "2_2") (pintype "passive"))
      (node (ref "U1") (pin "3") (pinfunction "VCP_3") (pintype "passive"))
    )
    (net (code "60") (name "Net-(U2-FB)") (class "Default")
      (node (ref "R1") (pin "1") (pinfunction "1_1") (pintype "passive"))
      (node (ref "R2") (pin "2") (pinfunction "2_2") (pintype "passive"))
      (node (ref "U2") (pin "3") (pinfunction "FB_3") (pintype "passive"))
    )
    (net (code "61") (name "Net-(U3-OUT)") (class "Default")
      (node (ref "HP8") (pin "1") (pinfunction "1_1") (pintype "passive"))
      (node (ref "U3") (pin "3") (pinfunction "OUT_3") (pintype "passive"))
    )
    (net (code "62") (name "Net-(U3-PGO)") (class "Default")
      (node (ref "R6") (pin "1") (pinfunction "1_1") (pintype "passive"))
      (node (ref "U3") (pin "5") (pinfunction "PGO_5") (pintype "passive"))
    )
    (net (code "63") (name "Net-(U7-~{RST})") (class "Default")
      (node (ref "R24") (pin "2") (pinfunction "2_2") (pintype "passive"))
      (node (ref "U7") (pin "9") (pinfunction "~{RST}_9") (pintype "passive"))
    )
    (net (code "64") (name "Net-(USBC1-CC1)") (class "Default")
      (node (ref "R11") (pin "1") (pinfunction "1_1") (pintype "passive"))
      (node (ref "USBC1") (pin "A5") (pinfunction "CC1_A5") (pintype "passive"))
    )
    (net (code "65") (name "Net-(USBC1-CC2)") (class "Default")
      (node (ref "R10") (pin "2") (pinfunction "2_2") (pintype "passive"))
      (node (ref "USBC1") (pin "B5") (pinfunction "CC2_B5") (pintype "passive"))
    )
    (net (code "66") (name "Net-(USBC2-CC1)") (class "Default")
      (node (ref "R22") (pin "1") (pinfunction "1_1") (pintype "passive"))
      (node (ref "USBC2") (pin "A5") (pinfunction "CC1_A5") (pintype "passive"))
    )
    (net (code "67") (name "Net-(USBC2-CC2)") (class "Default")
      (node (ref "R21") (pin "2") (pinfunction "2_2") (pintype "passive"))
      (node (ref "USBC2") (pin "B5") (pinfunction "CC2_B5") (pintype "passive"))
    )
    (net (code "68") (name "VCC") (class "Default")
      (node (ref "C1") (pin "2") (pinfunction "2_2") (pintype "passive"))
      (node (ref "C3") (pin "2") (pinfunction "2_2") (pintype "passive"))
      (node (ref "C30") (pin "2") (pinfunction "2_2") (pintype "passive"))
      (node (ref "C31") (pin "2") (pinfunction "2_2") (pintype "passive"))
      (node (ref "C4") (pin "2") (pinfunction "2_2") (pintype "passive"))
      (node (ref "C8") (pin "1") (pinfunction "1_1") (pintype "passive"))
      (node (ref "D1") (pin "2") (pinfunction "K_2") (pintype "passive"))
      (node (ref "R1") (pin "2") (pinfunction "2_2") (pintype "passive"))
      (node (ref "U1") (pin "11") (pinfunction "VM_11") (pintype "passive"))
      (node (ref "U1") (pin "4") (pinfunction "VM_4") (pintype "passive"))
    )
    (net (code "69") (name "unconnected-(L3-Pad2)") (class "Default")
      (node (ref "L3") (pin "2") (pinfunction "2_2") (pintype "passive"))
    )
    (net (code "70") (name "unconnected-(U2-NC-Pad6)") (class "Default")
      (node (ref "U2") (pin "6") (pinfunction "NC_6") (pintype "passive+no_connect"))
    )
    (net (code "71") (name "unconnected-(U4-NC-Pad4)") (class "Default")
      (node (ref "U4") (pin "4") (pinfunction "NC_4") (pintype "passive+no_connect"))
    )
    (net (code "72") (name "unconnected-(U7-CTS-Pad23)") (class "Default")
      (node (ref "U7") (pin "23") (pinfunction "CTS_23") (pintype "passive+no_connect"))
    )
    (net (code "73") (name "unconnected-(U7-DCD-Pad1)") (class "Default")
      (node (ref "U7") (pin "1") (pinfunction "DCD_1") (pintype "passive+no_connect"))
    )
    (net (code "74") (name "unconnected-(U7-DSR-Pad27)") (class "Default")
      (node (ref "U7") (pin "27") (pinfunction "DSR_27") (pintype "passive+no_connect"))
    )
    (net (code "75") (name "unconnected-(U7-NC-Pad10)") (class "Default")
      (node (ref "U7") (pin "10") (pinfunction "NC_10") (pintype "passive+no_connect"))
    )
    (net (code "76") (name "unconnected-(U7-NC-Pad13)") (class "Default")
      (node (ref "U7") (pin "13") (pinfunction "NC_13") (pintype "passive+no_connect"))
    )
    (net (code "77") (name "unconnected-(U7-NC-Pad14)") (class "Default")
      (node (ref "U7") (pin "14") (pinfunction "NC_14") (pintype "passive+no_connect"))
    )
    (net (code "78") (name "unconnected-(U7-NC-Pad15)") (class "Default")
      (node (ref "U7") (pin "15") (pinfunction "NC_15") (pintype "passive+no_connect"))
    )
    (net (code "79") (name "unconnected-(U7-NC-Pad16)") (class "Default")
      (node (ref "U7") (pin "16") (pinfunction "NC_16") (pintype "passive+no_connect"))
    )
    (net (code "80") (name "unconnected-(U7-NC-Pad17)") (class "Default")
      (node (ref "U7") (pin "17") (pinfunction "NC_17") (pintype "passive+no_connect"))
    )
    (net (code "81") (name "unconnected-(U7-NC-Pad19)") (class "Default")
      (node (ref "U7") (pin "19") (pinfunction "NC_19") (pintype "passive+no_connect"))
    )
    (net (code "82") (name "unconnected-(U7-NC-Pad20)") (class "Default")
      (node (ref "U7") (pin "20") (pinfunction "NC_20") (pintype "passive+no_connect"))
    )
    (net (code "83") (name "unconnected-(U7-NC-Pad21)") (class "Default")
      (node (ref "U7") (pin "21") (pinfunction "NC_21") (pintype "passive+no_connect"))
    )
    (net (code "84") (name "unconnected-(U7-NC-Pad22)") (class "Default")
      (node (ref "U7") (pin "22") (pinfunction "NC_22") (pintype "passive+no_connect"))
    )
    (net (code "85") (name "unconnected-(U7-NC{slash}VPP-Pad18)") (class "Default")
      (node (ref "U7") (pin "18") (pinfunction "NC/VPP_18") (pintype "passive+no_connect"))
    )
    (net (code "86") (name "unconnected-(U7-RI-Pad2)") (class "Default")
      (node (ref "U7") (pin "2") (pinfunction "RI_2") (pintype "passive+no_connect"))
    )
    (net (code "87") (name "unconnected-(U7-SUSPEND-Pad12)") (class "Default")
      (node (ref "U7") (pin "12") (pinfunction "SUSPEND_12") (pintype "passive+no_connect"))
    )
    (net (code "88") (name "unconnected-(U7-~{SUSPEND}-Pad11)") (class "Default")
      (node (ref "U7") (pin "11") (pinfunction "~{SUSPEND}_11") (pintype "passive+no_connect"))
    )
    (net (code "89") (name "unconnected-(U8-NC-Pad4)") (class "Default")
      (node (ref "U8") (pin "4") (pinfunction "NC_4") (pintype "passive+no_connect"))
    )
    (net (code "90") (name "unconnected-(USBC1-SBU1-PadA8)") (class "Default")
      (node (ref "USBC1") (pin "A8") (pinfunction "SBU1_A8") (pintype "passive+no_connect"))
    )
    (net (code "91") (name "unconnected-(USBC1-SBU2-PadB8)") (class "Default")
      (node (ref "USBC1") (pin "B8") (pinfunction "SBU2_B8") (pintype "passive+no_connect"))
    )
    (net (code "92") (name "unconnected-(USBC2-SBU1-PadA8)") (class "Default")
      (node (ref "USBC2") (pin "A8") (pinfunction "SBU1_A8") (pintype "passive+no_connect"))
    )
    (net (code "93") (name "unconnected-(USBC2-SBU2-PadB8)") (class "Default")
      (node (ref "USBC2") (pin "B8") (pinfunction "SBU2_B8") (pintype "passive+no_connect"))
    )
  )
)
